# Motor_Driver.net
KiCad netlist of a schematic drawn in Altium Designer
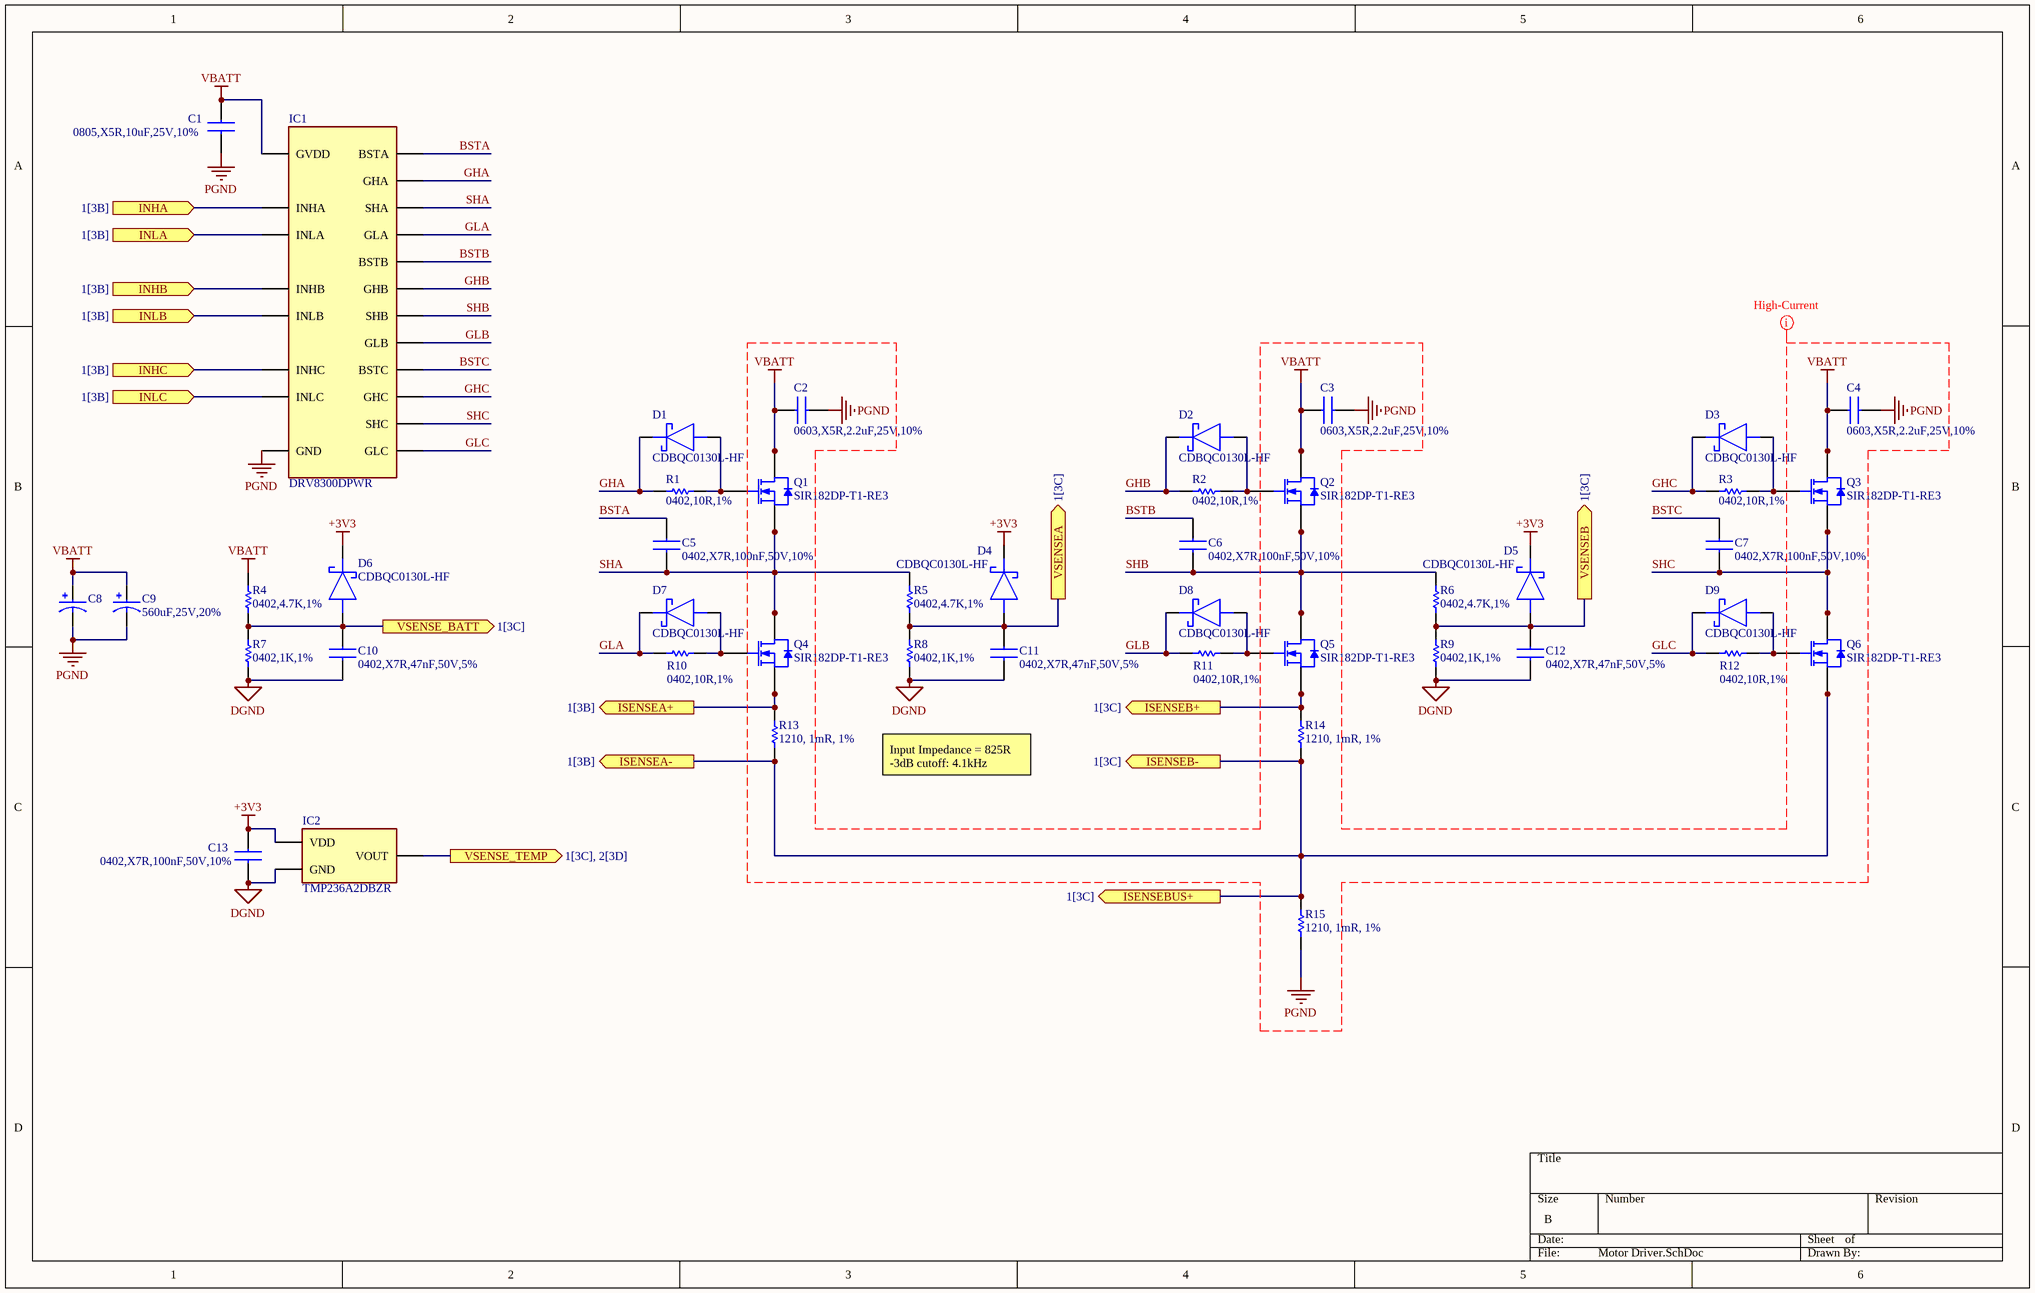
[diagram p0: Motor Driver.SchDoc]

(export (version "E")
  (design (tool "Eeschema 10.0.6"))
  (components
    (comp (ref "C1")
      (value "0805,X5R,10uF,25V,10%")
      (footprint "CAPC2012X145N")
      (description "10 µF ±10% 25V Ceramic Capacitor X5R 0805 (2012 Metric)")
      (fields
        (field (name "MANUFACTURER_PART_NUMBER") "CC0805KKX5R8BB106")
        (field (name "MOUSER PART NUMBER") "603-CC805KKX5R8BB106")
      )
      (libsource (lib "ESC") (part "CC0805KKX5R8BB106"))
    )
    (comp (ref "C2")
      (value "0603,X5R,2.2uF,25V,10%")
      (footprint "CAPC1608X90N")
      (description "2.2 µF ±10% 25V Ceramic Capacitor X5R 0603 (1608 Metric)")
      (fields
        (field (name "MANUFACTURER_PART_NUMBER") "CC0603JRNPO9BN560")
        (field (name "MOUSER PART NUMBER") "603-CC603KRX7R9BB105")
      )
      (libsource (lib "ESC") (part "CC0603KRX5R8BB225"))
    )
    (comp (ref "C3")
      (value "0603,X5R,2.2uF,25V,10%")
      (footprint "CAPC1608X90N")
      (description "2.2 µF ±10% 25V Ceramic Capacitor X5R 0603 (1608 Metric)")
      (fields
        (field (name "MANUFACTURER_PART_NUMBER") "CC0603JRNPO9BN560")
        (field (name "MOUSER PART NUMBER") "603-CC603KRX7R9BB105")
      )
      (libsource (lib "ESC") (part "CC0603KRX5R8BB225"))
    )
    (comp (ref "C4")
      (value "0603,X5R,2.2uF,25V,10%")
      (footprint "CAPC1608X90N")
      (description "2.2 µF ±10% 25V Ceramic Capacitor X5R 0603 (1608 Metric)")
      (fields
        (field (name "MANUFACTURER_PART_NUMBER") "CC0603JRNPO9BN560")
        (field (name "MOUSER PART NUMBER") "603-CC603KRX7R9BB105")
      )
      (libsource (lib "ESC") (part "CC0603KRX5R8BB225"))
    )
    (comp (ref "C5")
      (value "0402,X7R,100nF,50V,10%")
      (footprint "CAPC1005X55N")
      (description "0.1 µF ±10% 50V Ceramic Capacitor X7R 0402 (1005 Metric)")
      (fields
        (field (name "MANUFACTURER_PART_NUMBER") "CC0402KRX7R9BB104")
        (field (name "MOUSER PART NUMBER") "603-CC402KRX7R9BB104")
      )
      (libsource (lib "ESC") (part "CC0402KRX7R9BB104"))
    )
    (comp (ref "C6")
      (value "0402,X7R,100nF,50V,10%")
      (footprint "CAPC1005X55N")
      (description "0.1 µF ±10% 50V Ceramic Capacitor X7R 0402 (1005 Metric)")
      (fields
        (field (name "MANUFACTURER_PART_NUMBER") "CC0402KRX7R9BB104")
        (field (name "MOUSER PART NUMBER") "603-CC402KRX7R9BB104")
      )
      (libsource (lib "ESC") (part "CC0402KRX7R9BB104"))
    )
    (comp (ref "C7")
      (value "0402,X7R,100nF,50V,10%")
      (footprint "CAPC1005X55N")
      (description "0.1 µF ±10% 50V Ceramic Capacitor X7R 0402 (1005 Metric)")
      (fields
        (field (name "MANUFACTURER_PART_NUMBER") "CC0402KRX7R9BB104")
        (field (name "MOUSER PART NUMBER") "603-CC402KRX7R9BB104")
      )
      (libsource (lib "ESC") (part "CC0402KRX7R9BB104"))
    )
    (comp (ref "C8")
      (value "560uF,25V,20%")
      (footprint "CAP-SMD_BD8.0-L8.3-W8.3-FD")
      (description "25V 560uF ±20% SMD,D8xL10.5mm Aluminum - Polymer Capacitors RoHS")
      (fields (field (name "LCSC PART #") "C5246548") (field (name "MANU PART #") "HV1E567M0810PZ"))
      (libsource (lib "ESC") (part "HV1E567M0810PZ"))
    )
    (comp (ref "C9")
      (value "560uF,25V,20%")
      (footprint "CAP-SMD_BD8.0-L8.3-W8.3-FD")
      (description "25V 560uF ±20% SMD,D8xL10.5mm Aluminum - Polymer Capacitors RoHS")
      (fields (field (name "LCSC PART #") "C5246548") (field (name "MANU PART #") "HV1E567M0810PZ"))
      (libsource (lib "ESC") (part "HV1E567M0810PZ"))
    )
    (comp (ref "C10")
      (value "0402,X7R,47nF,50V,5%")
      (footprint "CAPC1005X55N")
      (description "0.047 µF ±5% 50V Ceramic Capacitor X7R 0402 (1005 Metric)")
      (fields
        (field (name "MANUFACTURER_PART_NUMBER") "CC0402JRX7R9BB473")
        (field (name "MOUSER PART NUMBER") "603-CC402KRX7R9BB104")
      )
      (libsource (lib "ESC") (part "CC0402JRX7R9BB473"))
    )
    (comp (ref "C11")
      (value "0402,X7R,47nF,50V,5%")
      (footprint "CAPC1005X55N")
      (description "0.047 µF ±5% 50V Ceramic Capacitor X7R 0402 (1005 Metric)")
      (fields
        (field (name "MANUFACTURER_PART_NUMBER") "CC0402JRX7R9BB473")
        (field (name "MOUSER PART NUMBER") "603-CC402KRX7R9BB104")
      )
      (libsource (lib "ESC") (part "CC0402JRX7R9BB473"))
    )
    (comp (ref "C12")
      (value "0402,X7R,47nF,50V,5%")
      (footprint "CAPC1005X55N")
      (description "0.047 µF ±5% 50V Ceramic Capacitor X7R 0402 (1005 Metric)")
      (fields
        (field (name "MANUFACTURER_PART_NUMBER") "CC0402JRX7R9BB473")
        (field (name "MOUSER PART NUMBER") "603-CC402KRX7R9BB104")
      )
      (libsource (lib "ESC") (part "CC0402JRX7R9BB473"))
    )
    (comp (ref "C13")
      (value "0402,X7R,100nF,50V,10%")
      (footprint "CAPC1005X55N")
      (description "0.1 µF ±10% 50V Ceramic Capacitor X7R 0402 (1005 Metric)")
      (fields
        (field (name "MANUFACTURER_PART_NUMBER") "CC0402KRX7R9BB104")
        (field (name "MOUSER PART NUMBER") "603-CC402KRX7R9BB104")
      )
      (libsource (lib "ESC") (part "CC0402KRX7R9BB104"))
    )
    (comp (ref "D1")
      (value "CDBQC0130L-HF")
      (footprint "CDBQC0130LHF")
      (description "Diode 30 V 100mA Surface Mount 0402C/SOD-923F")
      (fields (field (name "MOUSER PART NUMBER") "750-CDBQC0130L-HF") (field (name "LCSC PART #") "C2886012"))
      (libsource (lib "ESC") (part "CDBQC0130L-HF"))
    )
    (comp (ref "D2")
      (value "CDBQC0130L-HF")
      (footprint "CDBQC0130LHF")
      (description "Diode 30 V 100mA Surface Mount 0402C/SOD-923F")
      (fields (field (name "MOUSER PART NUMBER") "750-CDBQC0130L-HF") (field (name "LCSC PART #") "C2886012"))
      (libsource (lib "ESC") (part "CDBQC0130L-HF"))
    )
    (comp (ref "D3")
      (value "CDBQC0130L-HF")
      (footprint "CDBQC0130LHF")
      (description "Diode 30 V 100mA Surface Mount 0402C/SOD-923F")
      (fields (field (name "MOUSER PART NUMBER") "750-CDBQC0130L-HF") (field (name "LCSC PART #") "C2886012"))
      (libsource (lib "ESC") (part "CDBQC0130L-HF"))
    )
    (comp (ref "D4")
      (value "CDBQC0130L-HF")
      (footprint "CDBQC0130LHF")
      (description "Diode 30 V 100mA Surface Mount 0402C/SOD-923F")
      (fields (field (name "MOUSER PART NUMBER") "750-CDBQC0130L-HF") (field (name "LCSC PART #") "C2886012"))
      (libsource (lib "ESC") (part "CDBQC0130L-HF"))
    )
    (comp (ref "D5")
      (value "CDBQC0130L-HF")
      (footprint "CDBQC0130LHF")
      (description "Diode 30 V 100mA Surface Mount 0402C/SOD-923F")
      (fields (field (name "MOUSER PART NUMBER") "750-CDBQC0130L-HF") (field (name "LCSC PART #") "C2886012"))
      (libsource (lib "ESC") (part "CDBQC0130L-HF"))
    )
    (comp (ref "D6")
      (value "CDBQC0130L-HF")
      (footprint "CDBQC0130LHF")
      (description "Diode 30 V 100mA Surface Mount 0402C/SOD-923F")
      (fields (field (name "MOUSER PART NUMBER") "750-CDBQC0130L-HF") (field (name "LCSC PART #") "C2886012"))
      (libsource (lib "ESC") (part "CDBQC0130L-HF"))
    )
    (comp (ref "D7")
      (value "CDBQC0130L-HF")
      (footprint "CDBQC0130LHF")
      (description "Diode 30 V 100mA Surface Mount 0402C/SOD-923F")
      (fields (field (name "MOUSER PART NUMBER") "750-CDBQC0130L-HF") (field (name "LCSC PART #") "C2886012"))
      (libsource (lib "ESC") (part "CDBQC0130L-HF"))
    )
    (comp (ref "D8")
      (value "CDBQC0130L-HF")
      (footprint "CDBQC0130LHF")
      (description "Diode 30 V 100mA Surface Mount 0402C/SOD-923F")
      (fields (field (name "MOUSER PART NUMBER") "750-CDBQC0130L-HF") (field (name "LCSC PART #") "C2886012"))
      (libsource (lib "ESC") (part "CDBQC0130L-HF"))
    )
    (comp (ref "D9")
      (value "CDBQC0130L-HF")
      (footprint "CDBQC0130LHF")
      (description "Diode 30 V 100mA Surface Mount 0402C/SOD-923F")
      (fields (field (name "MOUSER PART NUMBER") "750-CDBQC0130L-HF") (field (name "LCSC PART #") "C2886012"))
      (libsource (lib "ESC") (part "CDBQC0130L-HF"))
    )
    (comp (ref "IC1")
      (value "DRV8300DPWR")
      (footprint "ESC:SOP65P640X120-20N")
      (description "TSSOP-20 Brushless DC (BLDC) Motor Driver ROHS")
      (fields (field (name "MOUSER PART NUMBER") "595-DRV8300DPWR") (field (name "LCSC PART #") "C3036056"))
      (libsource (lib "ESC") (part "DRV8300DPWR"))
    )
    (comp (ref "IC2")
      (value "TMP236A2DBZR")
      (footprint "SOT95P237X112-3N")
      (description "Low-power and high-precision analog output temperature sensor")
      (fields (field (name "MOUSER PART NUMBER") "595-TMP236A2DBZR") (field (name "LCSC PART #") "C2859666"))
      (libsource (lib "ESC") (part "TMP236A2DBZR"))
    )
    (comp (ref "Q1")
      (value "SIR182DP-T1-RE3")
      (footprint "POWERPAK-SO-8_L5.9-W4.9-P1.27-LS6.2-BL")
      (description "60V 117A 2.8mΩ@10V,15A 2V 1 N-Channel PowerPAKSO-8 MOSFETs ROHS")
      (fields (field (name "LCSC PART #") "C467943"))
      (libsource (lib "ESC") (part "SIR182DP-T1-RE3"))
    )
    (comp (ref "Q2")
      (value "SIR182DP-T1-RE3")
      (footprint "POWERPAK-SO-8_L5.9-W4.9-P1.27-LS6.2-BL")
      (description "60V 117A 2.8mΩ@10V,15A 2V 1 N-Channel PowerPAKSO-8 MOSFETs ROHS")
      (fields (field (name "LCSC PART #") "C467943"))
      (libsource (lib "ESC") (part "SIR182DP-T1-RE3"))
    )
    (comp (ref "Q3")
      (value "SIR182DP-T1-RE3")
      (footprint "POWERPAK-SO-8_L5.9-W4.9-P1.27-LS6.2-BL")
      (description "60V 117A 2.8mΩ@10V,15A 2V 1 N-Channel PowerPAKSO-8 MOSFETs ROHS")
      (fields (field (name "LCSC PART #") "C467943"))
      (libsource (lib "ESC") (part "SIR182DP-T1-RE3"))
    )
    (comp (ref "Q4")
      (value "SIR182DP-T1-RE3")
      (footprint "POWERPAK-SO-8_L5.9-W4.9-P1.27-LS6.2-BL")
      (description "60V 117A 2.8mΩ@10V,15A 2V 1 N-Channel PowerPAKSO-8 MOSFETs ROHS")
      (fields (field (name "LCSC PART #") "C467943"))
      (libsource (lib "ESC") (part "SIR182DP-T1-RE3"))
    )
    (comp (ref "Q5")
      (value "SIR182DP-T1-RE3")
      (footprint "POWERPAK-SO-8_L5.9-W4.9-P1.27-LS6.2-BL")
      (description "60V 117A 2.8mΩ@10V,15A 2V 1 N-Channel PowerPAKSO-8 MOSFETs ROHS")
      (fields (field (name "LCSC PART #") "C467943"))
      (libsource (lib "ESC") (part "SIR182DP-T1-RE3"))
    )
    (comp (ref "Q6")
      (value "SIR182DP-T1-RE3")
      (footprint "POWERPAK-SO-8_L5.9-W4.9-P1.27-LS6.2-BL")
      (description "60V 117A 2.8mΩ@10V,15A 2V 1 N-Channel PowerPAKSO-8 MOSFETs ROHS")
      (fields (field (name "LCSC PART #") "C467943"))
      (libsource (lib "ESC") (part "SIR182DP-T1-RE3"))
    )
    (comp (ref "R1")
      (value "0402,10R,1%")
      (footprint "RESC1005X40N")
      (description "10 Ohms ±1% 0.063W, 1/16W Chip Resistor 0402 (1005 Metric) Moisture Resistant Thick Film")
      (fields
        (field (name "MANUFACTURER_PART_NUMBER") "RC0402FR-0710KL")
        (field (name "MOUSER PART NUMBER") "603-RC0402FR-0710KL")
      )
      (libsource (lib "ESC") (part "RC0402FR-0710RL"))
    )
    (comp (ref "R2")
      (value "0402,10R,1%")
      (footprint "RESC1005X40N")
      (description "10 Ohms ±1% 0.063W, 1/16W Chip Resistor 0402 (1005 Metric) Moisture Resistant Thick Film")
      (fields
        (field (name "MANUFACTURER_PART_NUMBER") "RC0402FR-0710KL")
        (field (name "MOUSER PART NUMBER") "603-RC0402FR-0710KL")
      )
      (libsource (lib "ESC") (part "RC0402FR-0710RL"))
    )
    (comp (ref "R3")
      (value "0402,10R,1%")
      (footprint "RESC1005X40N")
      (description "10 Ohms ±1% 0.063W, 1/16W Chip Resistor 0402 (1005 Metric) Moisture Resistant Thick Film")
      (fields
        (field (name "MANUFACTURER_PART_NUMBER") "RC0402FR-0710KL")
        (field (name "MOUSER PART NUMBER") "603-RC0402FR-0710KL")
      )
      (libsource (lib "ESC") (part "RC0402FR-0710RL"))
    )
    (comp (ref "R4")
      (value "0402,4.7K,1%")
      (footprint "RESC1005X40N")
      (description "4.7 kOhms ±1% 0.063W, 1/16W Chip Resistor 0402 (1005 Metric) Moisture Resistant Thick Film")
      (fields
        (field (name "MANUFACTURER_PART_NUMBER") "RC0402FR-0710KL")
        (field (name "MOUSER PART NUMBER") "603-RC0402FR-0710KL")
      )
      (libsource (lib "ESC") (part "RC0402FR-074K7L"))
    )
    (comp (ref "R5")
      (value "0402,4.7K,1%")
      (footprint "RESC1005X40N")
      (description "4.7 kOhms ±1% 0.063W, 1/16W Chip Resistor 0402 (1005 Metric) Moisture Resistant Thick Film")
      (fields
        (field (name "MANUFACTURER_PART_NUMBER") "RC0402FR-0710KL")
        (field (name "MOUSER PART NUMBER") "603-RC0402FR-0710KL")
      )
      (libsource (lib "ESC") (part "RC0402FR-074K7L"))
    )
    (comp (ref "R6")
      (value "0402,4.7K,1%")
      (footprint "RESC1005X40N")
      (description "4.7 kOhms ±1% 0.063W, 1/16W Chip Resistor 0402 (1005 Metric) Moisture Resistant Thick Film")
      (fields
        (field (name "MANUFACTURER_PART_NUMBER") "RC0402FR-0710KL")
        (field (name "MOUSER PART NUMBER") "603-RC0402FR-0710KL")
      )
      (libsource (lib "ESC") (part "RC0402FR-074K7L"))
    )
    (comp (ref "R7")
      (value "0402,1K,1%")
      (footprint "RESC1005X40N")
      (description "1 kOhms ±1% 0.063W, 1/16W Chip Resistor 0402 (1005 Metric) Moisture Resistant Thick Film")
      (fields
        (field (name "MANUFACTURER_PART_NUMBER") "RC0402FR-0710KL")
        (field (name "MOUSER PART NUMBER") "603-RC0402FR-0710KL")
      )
      (libsource (lib "ESC") (part "RC0402FR-071KL"))
    )
    (comp (ref "R8")
      (value "0402,1K,1%")
      (footprint "RESC1005X40N")
      (description "1 kOhms ±1% 0.063W, 1/16W Chip Resistor 0402 (1005 Metric) Moisture Resistant Thick Film")
      (fields
        (field (name "MANUFACTURER_PART_NUMBER") "RC0402FR-0710KL")
        (field (name "MOUSER PART NUMBER") "603-RC0402FR-0710KL")
      )
      (libsource (lib "ESC") (part "RC0402FR-071KL"))
    )
    (comp (ref "R9")
      (value "0402,1K,1%")
      (footprint "RESC1005X40N")
      (description "1 kOhms ±1% 0.063W, 1/16W Chip Resistor 0402 (1005 Metric) Moisture Resistant Thick Film")
      (fields
        (field (name "MANUFACTURER_PART_NUMBER") "RC0402FR-0710KL")
        (field (name "MOUSER PART NUMBER") "603-RC0402FR-0710KL")
      )
      (libsource (lib "ESC") (part "RC0402FR-071KL"))
    )
    (comp (ref "R10")
      (value "0402,10R,1%")
      (footprint "RESC1005X40N")
      (description "10 Ohms ±1% 0.063W, 1/16W Chip Resistor 0402 (1005 Metric) Moisture Resistant Thick Film")
      (fields
        (field (name "MANUFACTURER_PART_NUMBER") "RC0402FR-0710KL")
        (field (name "MOUSER PART NUMBER") "603-RC0402FR-0710KL")
      )
      (libsource (lib "ESC") (part "RC0402FR-0710RL"))
    )
    (comp (ref "R11")
      (value "0402,10R,1%")
      (footprint "RESC1005X40N")
      (description "10 Ohms ±1% 0.063W, 1/16W Chip Resistor 0402 (1005 Metric) Moisture Resistant Thick Film")
      (fields
        (field (name "MANUFACTURER_PART_NUMBER") "RC0402FR-0710KL")
        (field (name "MOUSER PART NUMBER") "603-RC0402FR-0710KL")
      )
      (libsource (lib "ESC") (part "RC0402FR-0710RL"))
    )
    (comp (ref "R12")
      (value "0402,10R,1%")
      (footprint "RESC1005X40N")
      (description "10 Ohms ±1% 0.063W, 1/16W Chip Resistor 0402 (1005 Metric) Moisture Resistant Thick Film")
      (fields
        (field (name "MANUFACTURER_PART_NUMBER") "RC0402FR-0710KL")
        (field (name "MOUSER PART NUMBER") "603-RC0402FR-0710KL")
      )
      (libsource (lib "ESC") (part "RC0402FR-0710RL"))
    )
    (comp (ref "R13")
      (value "1210, 1mR, 1%")
      (footprint "R1210")
      (description "1W 1mΩ Current Sense Resistor ±100ppm/℃ ±1% 1210 Current Sense Resistors / Shunt Resistors ROHS")
      (fields (field (name "LCSC PART #") "C509735"))
      (libsource (lib "ESC") (part "PMR25HZPFV1L00"))
    )
    (comp (ref "R14")
      (value "1210, 1mR, 1%")
      (footprint "R1210")
      (description "1W 1mΩ Current Sense Resistor ±100ppm/℃ ±1% 1210 Current Sense Resistors / Shunt Resistors ROHS")
      (fields (field (name "LCSC PART #") "C509735"))
      (libsource (lib "ESC") (part "PMR25HZPFV1L00"))
    )
    (comp (ref "R15")
      (value "1210, 1mR, 1%")
      (footprint "R1210")
      (description "1W 1mΩ Current Sense Resistor ±100ppm/℃ ±1% 1210 Current Sense Resistors / Shunt Resistors ROHS")
      (fields (field (name "LCSC PART #") "C509735"))
      (libsource (lib "ESC") (part "PMR25HZPFV1L00"))
    )
  )
  (nets
    (net (code "1") (name "+3V3") (class "Default")
      (node (ref "C13") (pin "2") (pinfunction "2_2") (pintype "passive"))
      (node (ref "D4") (pin "1") (pinfunction "K_1") (pintype "passive"))
      (node (ref "D5") (pin "1") (pinfunction "K_1") (pintype "passive"))
      (node (ref "D6") (pin "1") (pinfunction "K_1") (pintype "passive"))
      (node (ref "IC2") (pin "1") (pinfunction "VDD_1") (pintype "passive"))
    )
    (net (code "2") (name "/BSTA") (class "Default")
      (node (ref "C5") (pin "2") (pinfunction "2_2") (pintype "passive"))
      (node (ref "IC1") (pin "20") (pinfunction "BSTA_20") (pintype "passive"))
    )
    (net (code "3") (name "/BSTB") (class "Default")
      (node (ref "C6") (pin "2") (pinfunction "2_2") (pintype "passive"))
      (node (ref "IC1") (pin "17") (pinfunction "BSTB_17") (pintype "passive"))
    )
    (net (code "4") (name "/BSTC") (class "Default")
      (node (ref "C7") (pin "2") (pinfunction "2_2") (pintype "passive"))
      (node (ref "IC1") (pin "14") (pinfunction "BSTC_14") (pintype "passive"))
    )
    (net (code "5") (name "/GHA") (class "Default")
      (node (ref "D1") (pin "1") (pinfunction "K_1") (pintype "passive"))
      (node (ref "IC1") (pin "19") (pinfunction "GHA_19") (pintype "passive"))
      (node (ref "R1") (pin "1") (pinfunction "1_1") (pintype "passive"))
    )
    (net (code "6") (name "/GHB") (class "Default")
      (node (ref "D2") (pin "1") (pinfunction "K_1") (pintype "passive"))
      (node (ref "IC1") (pin "16") (pinfunction "GHB_16") (pintype "passive"))
      (node (ref "R2") (pin "1") (pinfunction "1_1") (pintype "passive"))
    )
    (net (code "7") (name "/GHC") (class "Default")
      (node (ref "D3") (pin "1") (pinfunction "K_1") (pintype "passive"))
      (node (ref "IC1") (pin "13") (pinfunction "GHC_13") (pintype "passive"))
      (node (ref "R3") (pin "1") (pinfunction "1_1") (pintype "passive"))
    )
    (net (code "8") (name "/GLA") (class "Default")
      (node (ref "D7") (pin "1") (pinfunction "K_1") (pintype "passive"))
      (node (ref "IC1") (pin "11") (pinfunction "GLA_11") (pintype "passive"))
      (node (ref "R10") (pin "1") (pinfunction "1_1") (pintype "passive"))
    )
    (net (code "9") (name "/GLB") (class "Default")
      (node (ref "D8") (pin "1") (pinfunction "K_1") (pintype "passive"))
      (node (ref "IC1") (pin "10") (pinfunction "GLB_10") (pintype "passive"))
      (node (ref "R11") (pin "1") (pinfunction "1_1") (pintype "passive"))
    )
    (net (code "10") (name "/GLC") (class "Default")
      (node (ref "D9") (pin "1") (pinfunction "K_1") (pintype "passive"))
      (node (ref "IC1") (pin "9") (pinfunction "GLC_9") (pintype "passive"))
      (node (ref "R12") (pin "1") (pinfunction "1_1") (pintype "passive"))
    )
    (net (code "11") (name "/INHA") (class "Default")
      (node (ref "IC1") (pin "1") (pinfunction "INHA_1") (pintype "passive"))
    )
    (net (code "12") (name "/INHB") (class "Default")
      (node (ref "IC1") (pin "2") (pinfunction "INHB_2") (pintype "passive"))
    )
    (net (code "13") (name "/INHC") (class "Default")
      (node (ref "IC1") (pin "3") (pinfunction "INHC_3") (pintype "passive"))
    )
    (net (code "14") (name "/INLA") (class "Default")
      (node (ref "IC1") (pin "4") (pinfunction "INLA_4") (pintype "passive"))
    )
    (net (code "15") (name "/INLB") (class "Default")
      (node (ref "IC1") (pin "5") (pinfunction "INLB_5") (pintype "passive"))
    )
    (net (code "16") (name "/INLC") (class "Default")
      (node (ref "IC1") (pin "6") (pinfunction "INLC_6") (pintype "passive"))
    )
    (net (code "17") (name "/ISENSEA+") (class "Default")
      (node (ref "Q4") (pin "1") (pinfunction "S_1") (pintype "passive"))
      (node (ref "Q4") (pin "2") (pinfunction "S_2") (pintype "passive"))
      (node (ref "Q4") (pin "3") (pinfunction "S_3") (pintype "passive"))
      (node (ref "R13") (pin "2") (pinfunction "2_2") (pintype "passive"))
    )
    (net (code "18") (name "/ISENSEA-") (class "Default")
      (node (ref "Q6") (pin "1") (pinfunction "S_1") (pintype "passive"))
      (node (ref "Q6") (pin "2") (pinfunction "S_2") (pintype "passive"))
      (node (ref "Q6") (pin "3") (pinfunction "S_3") (pintype "passive"))
      (node (ref "R13") (pin "1") (pinfunction "1_1") (pintype "passive"))
      (node (ref "R14") (pin "1") (pinfunction "1_1") (pintype "passive"))
      (node (ref "R15") (pin "2") (pinfunction "2_2") (pintype "passive"))
    )
    (net (code "19") (name "/ISENSEB+") (class "Default")
      (node (ref "Q5") (pin "1") (pinfunction "S_1") (pintype "passive"))
      (node (ref "Q5") (pin "2") (pinfunction "S_2") (pintype "passive"))
      (node (ref "Q5") (pin "3") (pinfunction "S_3") (pintype "passive"))
      (node (ref "R14") (pin "2") (pinfunction "2_2") (pintype "passive"))
    )
    (net (code "20") (name "/SHA") (class "Default")
      (node (ref "C5") (pin "1") (pinfunction "1_1") (pintype "passive"))
      (node (ref "IC1") (pin "18") (pinfunction "SHA_18") (pintype "passive"))
      (node (ref "Q1") (pin "1") (pinfunction "S_1") (pintype "passive"))
      (node (ref "Q1") (pin "2") (pinfunction "S_2") (pintype "passive"))
      (node (ref "Q1") (pin "3") (pinfunction "S_3") (pintype "passive"))
      (node (ref "Q4") (pin "5") (pinfunction "D_5") (pintype "passive"))
      (node (ref "Q4") (pin "6") (pinfunction "D_6") (pintype "passive"))
      (node (ref "Q4") (pin "7") (pinfunction "D_7") (pintype "passive"))
      (node (ref "Q4") (pin "8") (pinfunction "D_8") (pintype "passive"))
      (node (ref "R5") (pin "2") (pinfunction "2_2") (pintype "passive"))
    )
    (net (code "21") (name "/SHB") (class "Default")
      (node (ref "C6") (pin "1") (pinfunction "1_1") (pintype "passive"))
      (node (ref "IC1") (pin "15") (pinfunction "SHB_15") (pintype "passive"))
      (node (ref "Q2") (pin "1") (pinfunction "S_1") (pintype "passive"))
      (node (ref "Q2") (pin "2") (pinfunction "S_2") (pintype "passive"))
      (node (ref "Q2") (pin "3") (pinfunction "S_3") (pintype "passive"))
      (node (ref "Q5") (pin "5") (pinfunction "D_5") (pintype "passive"))
      (node (ref "Q5") (pin "6") (pinfunction "D_6") (pintype "passive"))
      (node (ref "Q5") (pin "7") (pinfunction "D_7") (pintype "passive"))
      (node (ref "Q5") (pin "8") (pinfunction "D_8") (pintype "passive"))
      (node (ref "R6") (pin "2") (pinfunction "2_2") (pintype "passive"))
    )
    (net (code "22") (name "/SHC") (class "Default")
      (node (ref "C7") (pin "1") (pinfunction "1_1") (pintype "passive"))
      (node (ref "IC1") (pin "12") (pinfunction "SHC_12") (pintype "passive"))
      (node (ref "Q3") (pin "1") (pinfunction "S_1") (pintype "passive"))
      (node (ref "Q3") (pin "2") (pinfunction "S_2") (pintype "passive"))
      (node (ref "Q3") (pin "3") (pinfunction "S_3") (pintype "passive"))
      (node (ref "Q6") (pin "5") (pinfunction "D_5") (pintype "passive"))
      (node (ref "Q6") (pin "6") (pinfunction "D_6") (pintype "passive"))
      (node (ref "Q6") (pin "7") (pinfunction "D_7") (pintype "passive"))
      (node (ref "Q6") (pin "8") (pinfunction "D_8") (pintype "passive"))
    )
    (net (code "23") (name "/VSENSEA") (class "Default")
      (node (ref "C11") (pin "2") (pinfunction "2_2") (pintype "passive"))
      (node (ref "D4") (pin "2") (pinfunction "A_2") (pintype "passive"))
      (node (ref "R5") (pin "1") (pinfunction "1_1") (pintype "passive"))
      (node (ref "R8") (pin "2") (pinfunction "2_2") (pintype "passive"))
    )
    (net (code "24") (name "/VSENSEB") (class "Default")
      (node (ref "C12") (pin "2") (pinfunction "2_2") (pintype "passive"))
      (node (ref "D5") (pin "2") (pinfunction "A_2") (pintype "passive"))
      (node (ref "R6") (pin "1") (pinfunction "1_1") (pintype "passive"))
      (node (ref "R9") (pin "2") (pinfunction "2_2") (pintype "passive"))
    )
    (net (code "25") (name "/VSENSE_BATT") (class "Default")
      (node (ref "C10") (pin "2") (pinfunction "2_2") (pintype "passive"))
      (node (ref "D6") (pin "2") (pinfunction "A_2") (pintype "passive"))
      (node (ref "R4") (pin "1") (pinfunction "1_1") (pintype "passive"))
      (node (ref "R7") (pin "2") (pinfunction "2_2") (pintype "passive"))
    )
    (net (code "26") (name "/VSENSE_TEMP") (class "Default")
      (node (ref "IC2") (pin "2") (pinfunction "VOUT_2") (pintype "passive"))
    )
    (net (code "27") (name "DGND") (class "Default")
      (node (ref "C10") (pin "1") (pinfunction "1_1") (pintype "passive"))
      (node (ref "C11") (pin "1") (pinfunction "1_1") (pintype "passive"))
      (node (ref "C12") (pin "1") (pinfunction "1_1") (pintype "passive"))
      (node (ref "C13") (pin "1") (pinfunction "1_1") (pintype "passive"))
      (node (ref "IC2") (pin "3") (pinfunction "GND_3") (pintype "passive"))
      (node (ref "R7") (pin "1") (pinfunction "1_1") (pintype "passive"))
      (node (ref "R8") (pin "1") (pinfunction "1_1") (pintype "passive"))
      (node (ref "R9") (pin "1") (pinfunction "1_1") (pintype "passive"))
    )
    (net (code "28") (name "Net-(D1-A)") (class "Default")
      (node (ref "D1") (pin "2") (pinfunction "A_2") (pintype "passive"))
      (node (ref "Q1") (pin "4") (pinfunction "G_4") (pintype "passive"))
      (node (ref "R1") (pin "2") (pinfunction "2_2") (pintype "passive"))
    )
    (net (code "29") (name "Net-(D2-A)") (class "Default")
      (node (ref "D2") (pin "2") (pinfunction "A_2") (pintype "passive"))
      (node (ref "Q2") (pin "4") (pinfunction "G_4") (pintype "passive"))
      (node (ref "R2") (pin "2") (pinfunction "2_2") (pintype "passive"))
    )
    (net (code "30") (name "Net-(D3-A)") (class "Default")
      (node (ref "D3") (pin "2") (pinfunction "A_2") (pintype "passive"))
      (node (ref "Q3") (pin "4") (pinfunction "G_4") (pintype "passive"))
      (node (ref "R3") (pin "2") (pinfunction "2_2") (pintype "passive"))
    )
    (net (code "31") (name "Net-(D7-A)") (class "Default")
      (node (ref "D7") (pin "2") (pinfunction "A_2") (pintype "passive"))
      (node (ref "Q4") (pin "4") (pinfunction "G_4") (pintype "passive"))
      (node (ref "R10") (pin "2") (pinfunction "2_2") (pintype "passive"))
    )
    (net (code "32") (name "Net-(D8-A)") (class "Default")
      (node (ref "D8") (pin "2") (pinfunction "A_2") (pintype "passive"))
      (node (ref "Q5") (pin "4") (pinfunction "G_4") (pintype "passive"))
      (node (ref "R11") (pin "2") (pinfunction "2_2") (pintype "passive"))
    )
    (net (code "33") (name "Net-(D9-A)") (class "Default")
      (node (ref "D9") (pin "2") (pinfunction "A_2") (pintype "passive"))
      (node (ref "Q6") (pin "4") (pinfunction "G_4") (pintype "passive"))
      (node (ref "R12") (pin "2") (pinfunction "2_2") (pintype "passive"))
    )
    (net (code "34") (name "PGND") (class "Default")
      (node (ref "C1") (pin "2") (pinfunction "2_2") (pintype "passive"))
      (node (ref "C2") (pin "2") (pinfunction "2_2") (pintype "passive"))
      (node (ref "C3") (pin "2") (pinfunction "2_2") (pintype "passive"))
      (node (ref "C4") (pin "2") (pinfunction "2_2") (pintype "passive"))
      (node (ref "C8") (pin "2") (pinfunction "2_2") (pintype "passive"))
      (node (ref "C9") (pin "2") (pinfunction "2_2") (pintype "passive"))
      (node (ref "IC1") (pin "8") (pinfunction "GND_8") (pintype "passive"))
      (node (ref "R15") (pin "1") (pinfunction "1_1") (pintype "passive"))
    )
    (net (code "35") (name "VBATT") (class "Default")
      (node (ref "C1") (pin "1") (pinfunction "1_1") (pintype "passive"))
      (node (ref "C2") (pin "1") (pinfunction "1_1") (pintype "passive"))
      (node (ref "C3") (pin "1") (pinfunction "1_1") (pintype "passive"))
      (node (ref "C4") (pin "1") (pinfunction "1_1") (pintype "passive"))
      (node (ref "C8") (pin "1") (pinfunction "1_1") (pintype "passive"))
      (node (ref "C9") (pin "1") (pinfunction "1_1") (pintype "passive"))
      (node (ref "IC1") (pin "7") (pinfunction "GVDD_7") (pintype "passive"))
      (node (ref "Q1") (pin "5") (pinfunction "D_5") (pintype "passive"))
      (node (ref "Q1") (pin "6") (pinfunction "D_6") (pintype "passive"))
      (node (ref "Q1") (pin "7") (pinfunction "D_7") (pintype "passive"))
      (node (ref "Q1") (pin "8") (pinfunction "D_8") (pintype "passive"))
      (node (ref "Q2") (pin "5") (pinfunction "D_5") (pintype "passive"))
      (node (ref "Q2") (pin "6") (pinfunction "D_6") (pintype "passive"))
      (node (ref "Q2") (pin "7") (pinfunction "D_7") (pintype "passive"))
      (node (ref "Q2") (pin "8") (pinfunction "D_8") (pintype "passive"))
      (node (ref "Q3") (pin "5") (pinfunction "D_5") (pintype "passive"))
      (node (ref "Q3") (pin "6") (pinfunction "D_6") (pintype "passive"))
      (node (ref "Q3") (pin "7") (pinfunction "D_7") (pintype "passive"))
      (node (ref "Q3") (pin "8") (pinfunction "D_8") (pintype "passive"))
      (node (ref "R4") (pin "2") (pinfunction "2_2") (pintype "passive"))
    )
  )
)
